# Sheet.net
KiCad netlist of a schematic drawn in Altium Designer
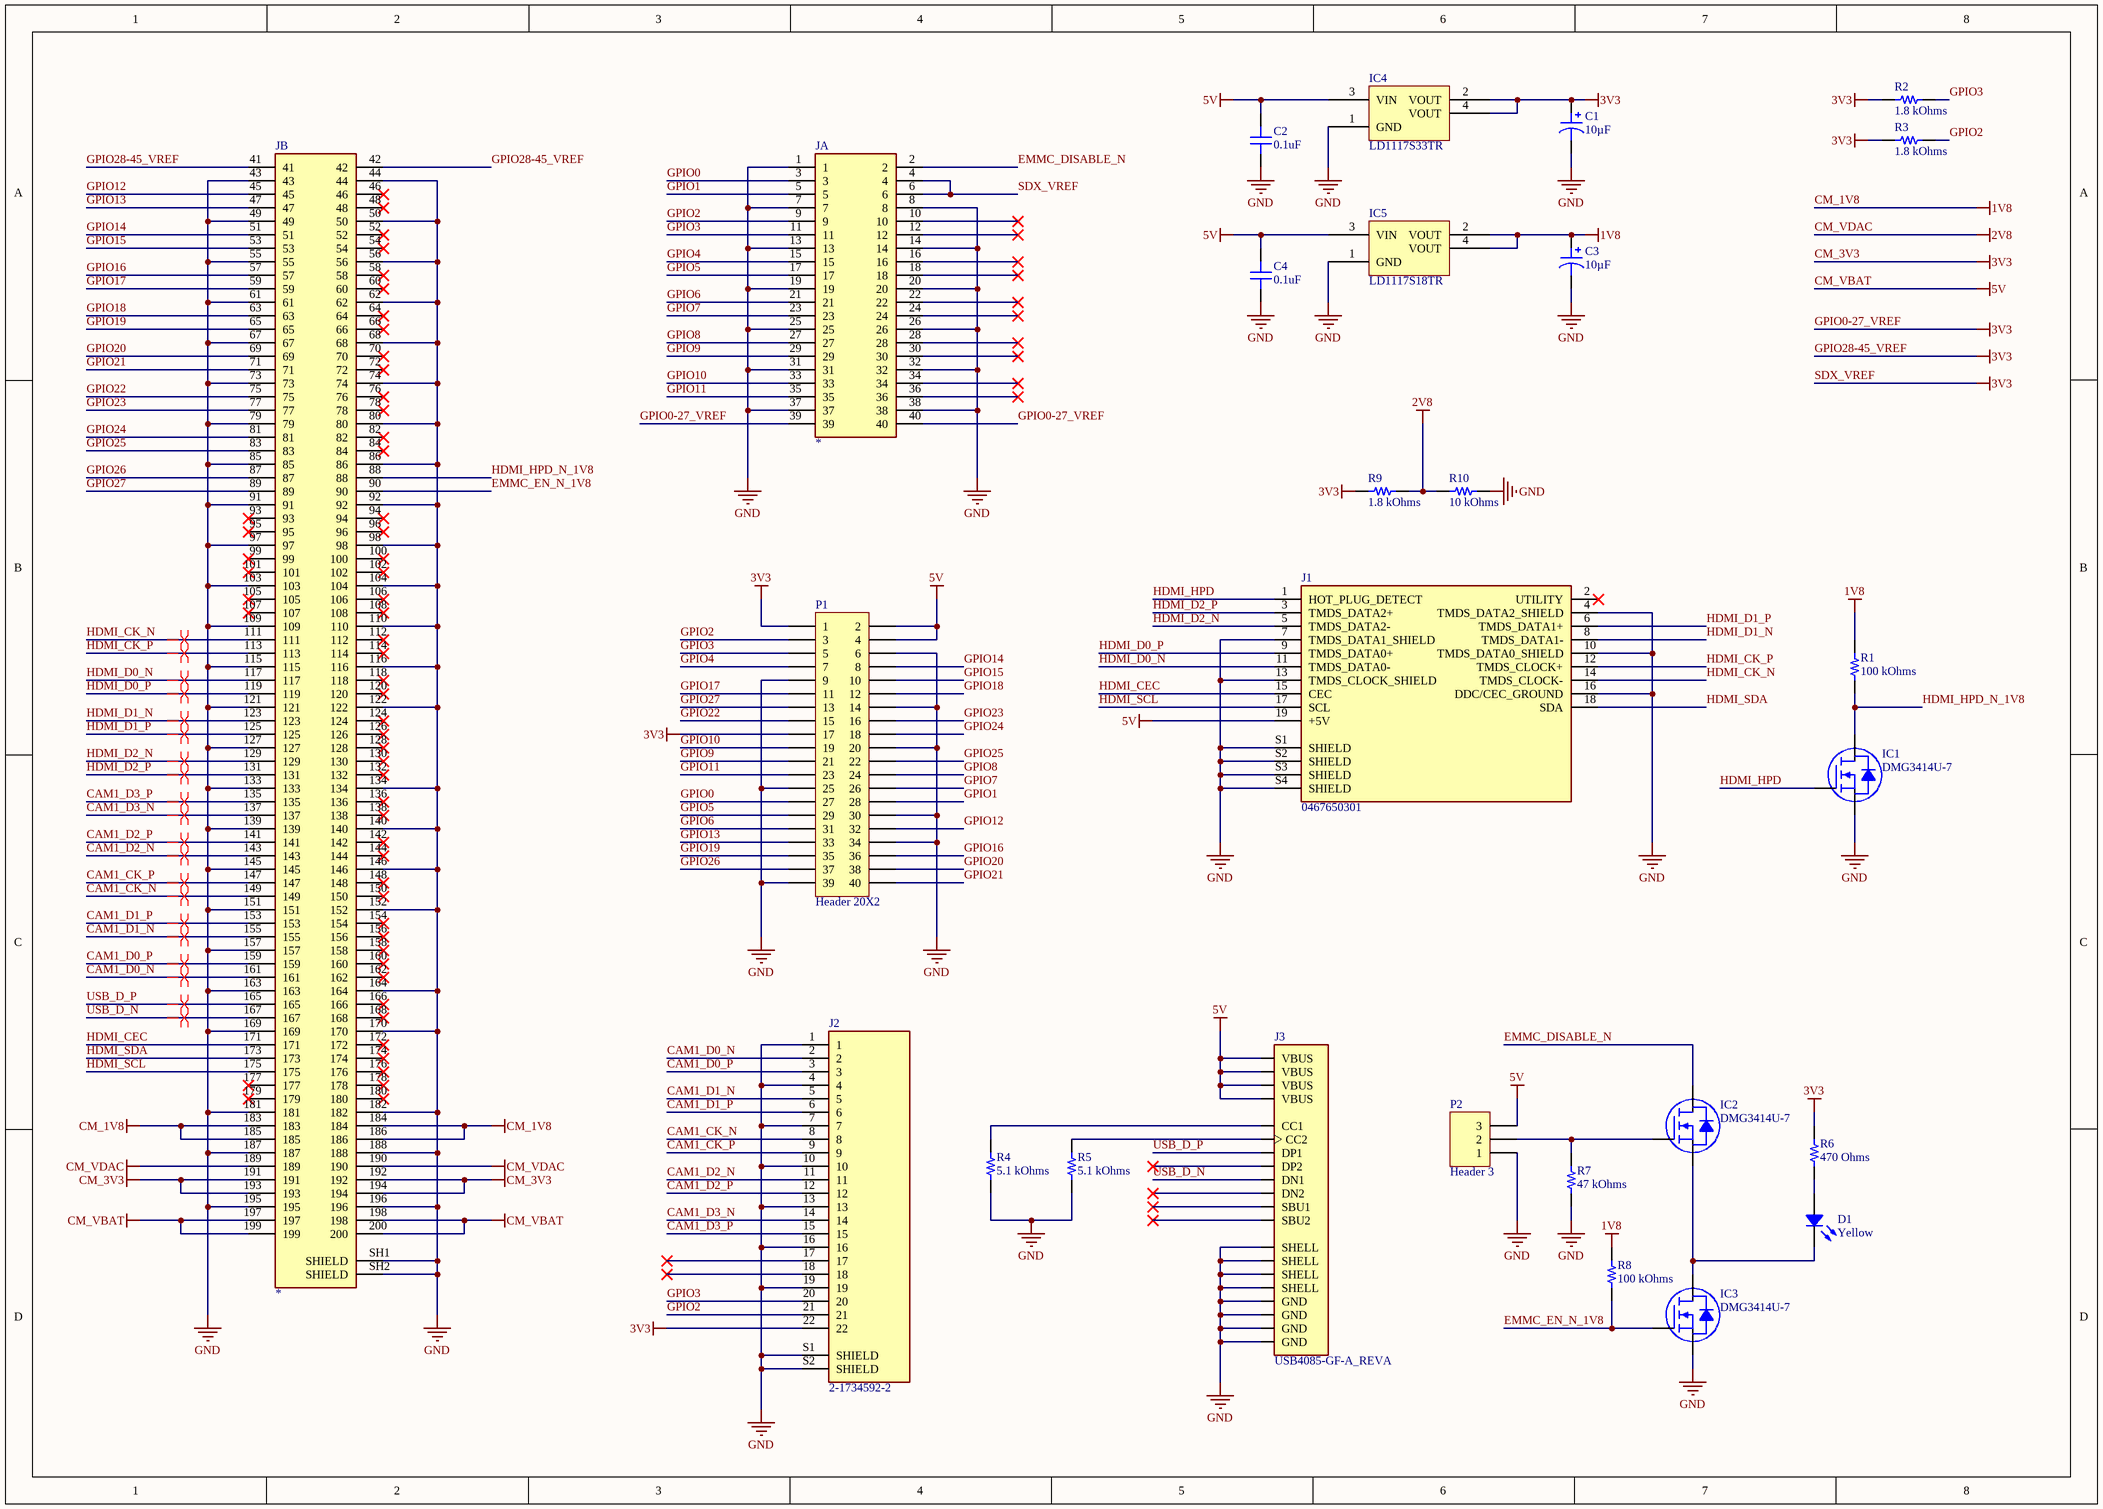
[diagram p0: Sheet.SchDoc]

(export (version "E")
  (design (tool "Eeschema 10.0.6"))
  (components
    (comp (ref "C1")
      (value "10µF")
      (footprint "CAP POL 1206_3216")
      (description "CAP TANT 4.7UF 10% 20V 1206")
      (fields (field (name "PART NUMBER") "TR3A475K020C1800") (field (name "MANUFACTURER") "Vishay Sprague"))
      (libsource (lib "Celestial Altium Library-altium_library") (part "Polarised Capacitor"))
    )
    (comp (ref "C2")
      (value "0.1uF")
      (footprint "CAP 0603_1608")
      (description "CAP CER 0.1uF 200V X7R 0603")
      (fields (field (name "PART NUMBER") "CC0603KRX7RABB102") (field (name "MANUFACTURER") "Yageo"))
      (libsource (lib "Celestial Altium Library-altium_library") (part "Capacitor"))
    )
    (comp (ref "C3")
      (value "10µF")
      (footprint "CAP POL 1206_3216")
      (description "CAP TANT 4.7UF 10% 20V 1206")
      (fields (field (name "PART NUMBER") "TR3A475K020C1800") (field (name "MANUFACTURER") "Vishay Sprague"))
      (libsource (lib "Celestial Altium Library-altium_library") (part "Polarised Capacitor"))
    )
    (comp (ref "C4")
      (value "0.1uF")
      (footprint "CAP 0603_1608")
      (description "CAP CER 0.1uF 200V X7R 0603")
      (fields (field (name "PART NUMBER") "CC0603KRX7RABB102") (field (name "MANUFACTURER") "Yageo"))
      (libsource (lib "Celestial Altium Library-altium_library") (part "Capacitor"))
    )
    (comp (ref "D1")
      (value "Yellow")
      (footprint "LED 0603_1608 YELLOW")
      (description "LED YELLOW DIFFUSED SMD")
      (fields (field (name "PART NUMBER") "FKY1111C-TR") (field (name "MANUFACTURER") "Stanley Electric Co"))
      (libsource (lib "Celestial Altium Library-altium_library") (part "LED"))
    )
    (comp (ref "IC1")
      (value "DMG3414U-7")
      (footprint "DIODES SOT-23-3")
      (description "MOSFET N-CH 20V 4.2A SOT23")
      (fields (field (name "MANUFACTURER") "Diodes Incorporated"))
      (libsource (lib "Celestial Altium Library-altium_library") (part "DIODES INC MOSFET N-CH SOT-23-3"))
    )
    (comp (ref "IC2")
      (value "DMG3414U-7")
      (footprint "DIODES SOT-23-3")
      (description "MOSFET N-CH 20V 4.2A SOT23")
      (fields (field (name "MANUFACTURER") "Diodes Incorporated"))
      (libsource (lib "Celestial Altium Library-altium_library") (part "DIODES INC MOSFET N-CH SOT-23-3"))
    )
    (comp (ref "IC3")
      (value "DMG3414U-7")
      (footprint "DIODES SOT-23-3")
      (description "MOSFET N-CH 20V 4.2A SOT23")
      (fields (field (name "MANUFACTURER") "Diodes Incorporated"))
      (libsource (lib "Celestial Altium Library-altium_library") (part "DIODES INC MOSFET N-CH SOT-23-3"))
    )
    (comp (ref "IC4")
      (value "LD1117S33TR")
      (footprint "ST SOT-223")
      (description "IC REG LINEAR 3.3V 800MA SOT223")
      (fields (field (name "MANUFACTURER") "STMicroelectronics"))
      (libsource (lib "Celestial Altium Library-altium_library") (part "ST LD1117"))
    )
    (comp (ref "IC5")
      (value "LD1117S18TR")
      (footprint "ST SOT-223")
      (description "IC REG LINEAR 1.8V 800MA SOT223")
      (fields (field (name "MANUFACTURER") "STMicroelectronics"))
      (libsource (lib "Celestial Altium Library-altium_library") (part "ST LD1117"))
    )
    (comp (ref "J")
      (value "1473149-4")
      (footprint "TE_1473149-4")
      (description "200 Position Dual Row 0.60mm Surface Mount Right Angle DIMM Memory Socket")
      (fields (field (name "MF") "TE Connectivity") (field (name "COMMENT_1") "*"))
      (libsource (lib "1473149-4") (part "1473149-4"))
    )
    (comp (ref "J1")
      (value "0467650301")
      (footprint "MOLEX_0467650301")
      (description "HDMI - Micro Receptacle Connector 19 Position Surface Mount, Right Angle")
      (fields (field (name "MF") "Molex"))
      (libsource (lib "0467650301") (part "0467650301"))
    )
    (comp (ref "J2")
      (value "2-1734592-2")
      (footprint "TE_2-1734592-2")
      (description "22 Position FPC Connector Contacts, Bottom 0.020 _0.50mm_ Surface Mount, Right Angle")
      (fields (field (name "MF") "TE Connectivity"))
      (libsource (lib "2-1734592-2") (part "2-1734592-2"))
    )
    (comp (ref "J3")
      (value "USB4085-GF-A_REVA")
      (footprint "GCT_USB4085-GF-A_REVA")
      (description "USB-C (USB TYPE-C) USB 2.0 Receptacle Connector 24 (16+8 Dummy) Position Through Hole, Right Angle")
      (fields (field (name "MF") "Global Connector Technology") (field (name "MP") "USB4085-GF-A"))
      (libsource (lib "USB4085-GF-A_REVA") (part "USB4085-GF-A_REVA"))
    )
    (comp (ref "P1")
      (value "Header 20X2")
      (footprint "HDR2X20")
      (description "Header, 20-Pin, Dual row")
      (fields (field (name "PUBLISHER") "Altium Limited"))
      (libsource (lib "Miscellaneous Connectors") (part "Header 20X2"))
    )
    (comp (ref "P2")
      (value "Header 3")
      (footprint "HDR1X3")
      (description "Header, 3-Pin")
      (fields (field (name "PUBLISHER") "Altium Limited"))
      (libsource (lib "Miscellaneous Connectors") (part "Header 3"))
    )
    (comp (ref "R1")
      (value "100 kOhms")
      (footprint "RES 0603_1608")
      (description "RES 100K OHM 0.1% 1/16W 0603")
      (fields
        (field (name "PART NUMBER") "RNCS0603BKE100K")
        (field (name "MANUFACTURER") "Stackpole Electronics Inc")
      )
      (libsource (lib "Celestial Altium Library-altium_library") (part "Resistor"))
    )
    (comp (ref "R2")
      (value "1.8 kOhms")
      (footprint "RES 0603_1608")
      (description "RES 1.8K OHM 5% 1/10W 0603")
      (fields
        (field (name "PART NUMBER") "RMCF0603JT1K80")
        (field (name "MANUFACTURER") "Stackpole Electronics Inc")
      )
      (libsource (lib "Celestial Altium Library-altium_library") (part "Resistor"))
    )
    (comp (ref "R3")
      (value "1.8 kOhms")
      (footprint "RES 0603_1608")
      (description "RES 1.8K OHM 5% 1/10W 0603")
      (fields
        (field (name "PART NUMBER") "RMCF0603JT1K80")
        (field (name "MANUFACTURER") "Stackpole Electronics Inc")
      )
      (libsource (lib "Celestial Altium Library-altium_library") (part "Resistor"))
    )
    (comp (ref "R4")
      (value "5.1 kOhms")
      (footprint "RES 0603_1608")
      (description "RES 5.1K OHM 5% 1/10W 0603")
      (fields
        (field (name "PART NUMBER") "RMCF0603JG5K10")
        (field (name "MANUFACTURER") "Stackpole Electronics Inc")
      )
      (libsource (lib "Celestial Altium Library-altium_library") (part "Resistor"))
    )
    (comp (ref "R5")
      (value "5.1 kOhms")
      (footprint "RES 0603_1608")
      (description "RES 5.1K OHM 5% 1/10W 0603")
      (fields
        (field (name "PART NUMBER") "RMCF0603JG5K10")
        (field (name "MANUFACTURER") "Stackpole Electronics Inc")
      )
      (libsource (lib "Celestial Altium Library-altium_library") (part "Resistor"))
    )
    (comp (ref "R6")
      (value "470 Ohms")
      (footprint "RES 0603_1608")
      (description "RES 470 OHM 1% 1/10W 0603")
      (fields
        (field (name "PART NUMBER") "RMCF0603FT470R")
        (field (name "MANUFACTURER") "Stackpole Electronics Inc")
      )
      (libsource (lib "Celestial Altium Library-altium_library") (part "Resistor"))
    )
    (comp (ref "R7")
      (value "47 kOhms")
      (footprint "RES 0603_1608")
      (description "RES SMD 47K OHM 0.1% 1/16W 0603")
      (fields
        (field (name "PART NUMBER") "CPF0603B47KE")
        (field (name "MANUFACTURER") "TE Connectivity Passive Product")
      )
      (libsource (lib "Celestial Altium Library-altium_library") (part "Resistor"))
    )
    (comp (ref "R8")
      (value "100 kOhms")
      (footprint "RES 0603_1608")
      (description "RES 100K OHM 0.1% 1/16W 0603")
      (fields
        (field (name "PART NUMBER") "RNCS0603BKE100K")
        (field (name "MANUFACTURER") "Stackpole Electronics Inc")
      )
      (libsource (lib "Celestial Altium Library-altium_library") (part "Resistor"))
    )
    (comp (ref "R9")
      (value "1.8 kOhms")
      (footprint "RES 0603_1608")
      (description "RES 1.8K OHM 5% 1/10W 0603")
      (fields
        (field (name "PART NUMBER") "RMCF0603JT1K80")
        (field (name "MANUFACTURER") "Stackpole Electronics Inc")
      )
      (libsource (lib "Celestial Altium Library-altium_library") (part "Resistor"))
    )
    (comp (ref "R10")
      (value "10 kOhms")
      (footprint "RES 0603_1608")
      (description "RES 10K OHM 0.1% 1/16W 0603")
      (fields
        (field (name "PART NUMBER") "RNCS0603BKE10K0")
        (field (name "MANUFACTURER") "Stackpole Electronics Inc")
      )
      (libsource (lib "Celestial Altium Library-altium_library") (part "Resistor"))
    )
  )
  (nets
    (net (code "1") (name "/CAM1_CK_N") (class "Default")
      (node (ref "J") (pin "149") (pinfunction "149_149") (pintype "passive"))
      (node (ref "J2") (pin "8") (pinfunction "8_8") (pintype "passive"))
    )
    (net (code "2") (name "/CAM1_CK_P") (class "Default")
      (node (ref "J") (pin "147") (pinfunction "147_147") (pintype "passive"))
      (node (ref "J2") (pin "9") (pinfunction "9_9") (pintype "passive"))
    )
    (net (code "3") (name "/CAM1_D0_N") (class "Default")
      (node (ref "J") (pin "161") (pinfunction "161_161") (pintype "passive"))
      (node (ref "J2") (pin "2") (pinfunction "2_2") (pintype "passive"))
    )
    (net (code "4") (name "/CAM1_D0_P") (class "Default")
      (node (ref "J") (pin "159") (pinfunction "159_159") (pintype "passive"))
      (node (ref "J2") (pin "3") (pinfunction "3_3") (pintype "passive"))
    )
    (net (code "5") (name "/CAM1_D1_N") (class "Default")
      (node (ref "J") (pin "155") (pinfunction "155_155") (pintype "passive"))
      (node (ref "J2") (pin "5") (pinfunction "5_5") (pintype "passive"))
    )
    (net (code "6") (name "/CAM1_D1_P") (class "Default")
      (node (ref "J") (pin "153") (pinfunction "153_153") (pintype "passive"))
      (node (ref "J2") (pin "6") (pinfunction "6_6") (pintype "passive"))
    )
    (net (code "7") (name "/CAM1_D2_N") (class "Default")
      (node (ref "J") (pin "143") (pinfunction "143_143") (pintype "passive"))
      (node (ref "J2") (pin "11") (pinfunction "11_11") (pintype "passive"))
    )
    (net (code "8") (name "/CAM1_D2_P") (class "Default")
      (node (ref "J") (pin "141") (pinfunction "141_141") (pintype "passive"))
      (node (ref "J2") (pin "12") (pinfunction "12_12") (pintype "passive"))
    )
    (net (code "9") (name "/CAM1_D3_N") (class "Default")
      (node (ref "J") (pin "137") (pinfunction "137_137") (pintype "passive"))
      (node (ref "J2") (pin "14") (pinfunction "14_14") (pintype "passive"))
    )
    (net (code "10") (name "/CAM1_D3_P") (class "Default")
      (node (ref "J") (pin "135") (pinfunction "135_135") (pintype "passive"))
      (node (ref "J2") (pin "15") (pinfunction "15_15") (pintype "passive"))
    )
    (net (code "11") (name "/EMMC_DISABLE_N") (class "Default")
      (node (ref "IC2") (pin "3") (pinfunction "D_3") (pintype "passive"))
      (node (ref "J") (pin "2") (pinfunction "2_2") (pintype "passive"))
    )
    (net (code "12") (name "/EMMC_EN_N_1V8") (class "Default")
      (node (ref "IC3") (pin "1") (pinfunction "G_1") (pintype "passive"))
      (node (ref "J") (pin "90") (pinfunction "90_90") (pintype "passive"))
      (node (ref "R8") (pin "1") (pinfunction "1_1") (pintype "passive"))
    )
    (net (code "13") (name "/GPIO0") (class "Default")
      (node (ref "J") (pin "3") (pinfunction "3_3") (pintype "passive"))
      (node (ref "P1") (pin "27") (pinfunction "27_27") (pintype "passive"))
    )
    (net (code "14") (name "/GPIO1") (class "Default")
      (node (ref "J") (pin "5") (pinfunction "5_5") (pintype "passive"))
      (node (ref "P1") (pin "28") (pinfunction "28_28") (pintype "passive"))
    )
    (net (code "15") (name "/GPIO2") (class "Default")
      (node (ref "J") (pin "9") (pinfunction "9_9") (pintype "passive"))
      (node (ref "J2") (pin "21") (pinfunction "21_21") (pintype "passive"))
      (node (ref "P1") (pin "3") (pinfunction "3_3") (pintype "passive"))
      (node (ref "R3") (pin "2") (pinfunction "2_2") (pintype "passive"))
    )
    (net (code "16") (name "/GPIO3") (class "Default")
      (node (ref "J") (pin "11") (pinfunction "11_11") (pintype "passive"))
      (node (ref "J2") (pin "20") (pinfunction "20_20") (pintype "passive"))
      (node (ref "P1") (pin "5") (pinfunction "5_5") (pintype "passive"))
      (node (ref "R2") (pin "2") (pinfunction "2_2") (pintype "passive"))
    )
    (net (code "17") (name "/GPIO4") (class "Default")
      (node (ref "J") (pin "15") (pinfunction "15_15") (pintype "passive"))
      (node (ref "P1") (pin "7") (pinfunction "7_7") (pintype "passive"))
    )
    (net (code "18") (name "/GPIO5") (class "Default")
      (node (ref "J") (pin "17") (pinfunction "17_17") (pintype "passive"))
      (node (ref "P1") (pin "29") (pinfunction "29_29") (pintype "passive"))
    )
    (net (code "19") (name "/GPIO6") (class "Default")
      (node (ref "J") (pin "21") (pinfunction "21_21") (pintype "passive"))
      (node (ref "P1") (pin "31") (pinfunction "31_31") (pintype "passive"))
    )
    (net (code "20") (name "/GPIO7") (class "Default")
      (node (ref "J") (pin "23") (pinfunction "23_23") (pintype "passive"))
      (node (ref "P1") (pin "26") (pinfunction "26_26") (pintype "passive"))
    )
    (net (code "21") (name "/GPIO8") (class "Default")
      (node (ref "J") (pin "27") (pinfunction "27_27") (pintype "passive"))
      (node (ref "P1") (pin "24") (pinfunction "24_24") (pintype "passive"))
    )
    (net (code "22") (name "/GPIO9") (class "Default")
      (node (ref "J") (pin "29") (pinfunction "29_29") (pintype "passive"))
      (node (ref "P1") (pin "21") (pinfunction "21_21") (pintype "passive"))
    )
    (net (code "23") (name "/GPIO10") (class "Default")
      (node (ref "J") (pin "33") (pinfunction "33_33") (pintype "passive"))
      (node (ref "P1") (pin "19") (pinfunction "19_19") (pintype "passive"))
    )
    (net (code "24") (name "/GPIO11") (class "Default")
      (node (ref "J") (pin "35") (pinfunction "35_35") (pintype "passive"))
      (node (ref "P1") (pin "23") (pinfunction "23_23") (pintype "passive"))
    )
    (net (code "25") (name "/GPIO12") (class "Default")
      (node (ref "J") (pin "45") (pinfunction "45_45") (pintype "passive"))
      (node (ref "P1") (pin "32") (pinfunction "32_32") (pintype "passive"))
    )
    (net (code "26") (name "/GPIO13") (class "Default")
      (node (ref "J") (pin "47") (pinfunction "47_47") (pintype "passive"))
      (node (ref "P1") (pin "33") (pinfunction "33_33") (pintype "passive"))
    )
    (net (code "27") (name "/GPIO14") (class "Default")
      (node (ref "J") (pin "51") (pinfunction "51_51") (pintype "passive"))
      (node (ref "P1") (pin "8") (pinfunction "8_8") (pintype "passive"))
    )
    (net (code "28") (name "/GPIO15") (class "Default")
      (node (ref "J") (pin "53") (pinfunction "53_53") (pintype "passive"))
      (node (ref "P1") (pin "10") (pinfunction "10_10") (pintype "passive"))
    )
    (net (code "29") (name "/GPIO16") (class "Default")
      (node (ref "J") (pin "57") (pinfunction "57_57") (pintype "passive"))
      (node (ref "P1") (pin "36") (pinfunction "36_36") (pintype "passive"))
    )
    (net (code "30") (name "/GPIO17") (class "Default")
      (node (ref "J") (pin "59") (pinfunction "59_59") (pintype "passive"))
      (node (ref "P1") (pin "11") (pinfunction "11_11") (pintype "passive"))
    )
    (net (code "31") (name "/GPIO18") (class "Default")
      (node (ref "J") (pin "63") (pinfunction "63_63") (pintype "passive"))
      (node (ref "P1") (pin "12") (pinfunction "12_12") (pintype "passive"))
    )
    (net (code "32") (name "/GPIO19") (class "Default")
      (node (ref "J") (pin "65") (pinfunction "65_65") (pintype "passive"))
      (node (ref "P1") (pin "35") (pinfunction "35_35") (pintype "passive"))
    )
    (net (code "33") (name "/GPIO20") (class "Default")
      (node (ref "J") (pin "69") (pinfunction "69_69") (pintype "passive"))
      (node (ref "P1") (pin "38") (pinfunction "38_38") (pintype "passive"))
    )
    (net (code "34") (name "/GPIO21") (class "Default")
      (node (ref "J") (pin "71") (pinfunction "71_71") (pintype "passive"))
      (node (ref "P1") (pin "40") (pinfunction "40_40") (pintype "passive"))
    )
    (net (code "35") (name "/GPIO22") (class "Default")
      (node (ref "J") (pin "75") (pinfunction "75_75") (pintype "passive"))
      (node (ref "P1") (pin "15") (pinfunction "15_15") (pintype "passive"))
    )
    (net (code "36") (name "/GPIO23") (class "Default")
      (node (ref "J") (pin "77") (pinfunction "77_77") (pintype "passive"))
      (node (ref "P1") (pin "16") (pinfunction "16_16") (pintype "passive"))
    )
    (net (code "37") (name "/GPIO24") (class "Default")
      (node (ref "J") (pin "81") (pinfunction "81_81") (pintype "passive"))
      (node (ref "P1") (pin "18") (pinfunction "18_18") (pintype "passive"))
    )
    (net (code "38") (name "/GPIO25") (class "Default")
      (node (ref "J") (pin "83") (pinfunction "83_83") (pintype "passive"))
      (node (ref "P1") (pin "22") (pinfunction "22_22") (pintype "passive"))
    )
    (net (code "39") (name "/GPIO26") (class "Default")
      (node (ref "J") (pin "87") (pinfunction "87_87") (pintype "passive"))
      (node (ref "P1") (pin "37") (pinfunction "37_37") (pintype "passive"))
    )
    (net (code "40") (name "/GPIO27") (class "Default")
      (node (ref "J") (pin "89") (pinfunction "89_89") (pintype "passive"))
      (node (ref "P1") (pin "13") (pinfunction "13_13") (pintype "passive"))
    )
    (net (code "41") (name "/HDMI_CEC") (class "Default")
      (node (ref "J") (pin "171") (pinfunction "171_171") (pintype "passive"))
      (node (ref "J1") (pin "15") (pinfunction "CEC_15") (pintype "passive"))
    )
    (net (code "42") (name "/HDMI_CK_N") (class "Default")
      (node (ref "J") (pin "111") (pinfunction "111_111") (pintype "passive"))
      (node (ref "J1") (pin "14") (pinfunction "TMDS_CLOCK-_14") (pintype "passive"))
    )
    (net (code "43") (name "/HDMI_CK_P") (class "Default")
      (node (ref "J") (pin "113") (pinfunction "113_113") (pintype "passive"))
      (node (ref "J1") (pin "12") (pinfunction "TMDS_CLOCK+_12") (pintype "passive"))
    )
    (net (code "44") (name "/HDMI_D0_N") (class "Default")
      (node (ref "J") (pin "117") (pinfunction "117_117") (pintype "passive"))
      (node (ref "J1") (pin "11") (pinfunction "TMDS_DATA0-_11") (pintype "passive"))
    )
    (net (code "45") (name "/HDMI_D0_P") (class "Default")
      (node (ref "J") (pin "119") (pinfunction "119_119") (pintype "passive"))
      (node (ref "J1") (pin "9") (pinfunction "TMDS_DATA0+_9") (pintype "passive"))
    )
    (net (code "46") (name "/HDMI_D1_N") (class "Default")
      (node (ref "J") (pin "123") (pinfunction "123_123") (pintype "passive"))
      (node (ref "J1") (pin "8") (pinfunction "TMDS_DATA1-_8") (pintype "passive"))
    )
    (net (code "47") (name "/HDMI_D1_P") (class "Default")
      (node (ref "J") (pin "125") (pinfunction "125_125") (pintype "passive"))
      (node (ref "J1") (pin "6") (pinfunction "TMDS_DATA1+_6") (pintype "passive"))
    )
    (net (code "48") (name "/HDMI_D2_N") (class "Default")
      (node (ref "J") (pin "129") (pinfunction "129_129") (pintype "passive"))
      (node (ref "J1") (pin "5") (pinfunction "TMDS_DATA2-_5") (pintype "passive"))
    )
    (net (code "49") (name "/HDMI_D2_P") (class "Default")
      (node (ref "J") (pin "131") (pinfunction "131_131") (pintype "passive"))
      (node (ref "J1") (pin "3") (pinfunction "TMDS_DATA2+_3") (pintype "passive"))
    )
    (net (code "50") (name "/HDMI_HPD") (class "Default")
      (node (ref "IC1") (pin "1") (pinfunction "G_1") (pintype "passive"))
      (node (ref "J1") (pin "1") (pinfunction "HOT_PLUG_DETECT_1") (pintype "passive"))
    )
    (net (code "51") (name "/HDMI_HPD_N_1V8") (class "Default")
      (node (ref "IC1") (pin "3") (pinfunction "D_3") (pintype "passive"))
      (node (ref "J") (pin "88") (pinfunction "88_88") (pintype "passive"))
      (node (ref "R1") (pin "1") (pinfunction "1_1") (pintype "passive"))
    )
    (net (code "52") (name "/HDMI_SCL") (class "Default")
      (node (ref "J") (pin "175") (pinfunction "175_175") (pintype "passive"))
      (node (ref "J1") (pin "17") (pinfunction "SCL_17") (pintype "passive"))
    )
    (net (code "53") (name "/HDMI_SDA") (class "Default")
      (node (ref "J") (pin "173") (pinfunction "173_173") (pintype "passive"))
      (node (ref "J1") (pin "18") (pinfunction "SDA_18") (pintype "passive"))
    )
    (net (code "54") (name "/USB_D_N") (class "Default")
      (node (ref "J") (pin "167") (pinfunction "167_167") (pintype "passive"))
      (node (ref "J3") (pin "A7") (pinfunction "DN1_A7") (pintype "bidirectional"))
    )
    (net (code "55") (name "/USB_D_P") (class "Default")
      (node (ref "J") (pin "165") (pinfunction "165_165") (pintype "passive"))
      (node (ref "J3") (pin "A6") (pinfunction "DP1_A6") (pintype "bidirectional"))
    )
    (net (code "56") (name "1V8") (class "Default")
      (node (ref "C3") (pin "1") (pinfunction "1_1") (pintype "passive"))
      (node (ref "IC5") (pin "2") (pinfunction "VOUT_2") (pintype "passive"))
      (node (ref "IC5") (pin "4") (pinfunction "VOUT_4") (pintype "passive"))
      (node (ref "J") (pin "183") (pinfunction "183_183") (pintype "passive"))
      (node (ref "J") (pin "184") (pinfunction "184_184") (pintype "passive"))
      (node (ref "J") (pin "185") (pinfunction "185_185") (pintype "passive"))
      (node (ref "J") (pin "186") (pinfunction "186_186") (pintype "passive"))
      (node (ref "R1") (pin "2") (pinfunction "2_2") (pintype "passive"))
      (node (ref "R8") (pin "2") (pinfunction "2_2") (pintype "passive"))
    )
    (net (code "57") (name "2V8") (class "Default")
      (node (ref "J") (pin "189") (pinfunction "189_189") (pintype "passive"))
      (node (ref "J") (pin "190") (pinfunction "190_190") (pintype "passive"))
      (node (ref "R10") (pin "2") (pinfunction "2_2") (pintype "passive"))
      (node (ref "R9") (pin "1") (pinfunction "1_1") (pintype "passive"))
    )
    (net (code "58") (name "3V3") (class "Default")
      (node (ref "C1") (pin "1") (pinfunction "1_1") (pintype "passive"))
      (node (ref "IC4") (pin "2") (pinfunction "VOUT_2") (pintype "passive"))
      (node (ref "IC4") (pin "4") (pinfunction "VOUT_4") (pintype "passive"))
      (node (ref "J") (pin "191") (pinfunction "191_191") (pintype "passive"))
      (node (ref "J") (pin "192") (pinfunction "192_192") (pintype "passive"))
      (node (ref "J") (pin "193") (pinfunction "193_193") (pintype "passive"))
      (node (ref "J") (pin "194") (pinfunction "194_194") (pintype "passive"))
      (node (ref "J") (pin "39") (pinfunction "39_39") (pintype "passive"))
      (node (ref "J") (pin "4") (pinfunction "4_4") (pintype "passive"))
      (node (ref "J") (pin "40") (pinfunction "40_40") (pintype "passive"))
      (node (ref "J") (pin "41") (pinfunction "41_41") (pintype "passive"))
      (node (ref "J") (pin "42") (pinfunction "42_42") (pintype "passive"))
      (node (ref "J") (pin "6") (pinfunction "6_6") (pintype "passive"))
      (node (ref "J2") (pin "22") (pinfunction "22_22") (pintype "passive"))
      (node (ref "P1") (pin "1") (pinfunction "1_1") (pintype "passive"))
      (node (ref "P1") (pin "17") (pinfunction "17_17") (pintype "passive"))
      (node (ref "R2") (pin "1") (pinfunction "1_1") (pintype "passive"))
      (node (ref "R3") (pin "1") (pinfunction "1_1") (pintype "passive"))
      (node (ref "R6") (pin "2") (pinfunction "2_2") (pintype "passive"))
      (node (ref "R9") (pin "2") (pinfunction "2_2") (pintype "passive"))
    )
    (net (code "59") (name "5V") (class "Default")
      (node (ref "C2") (pin "2") (pinfunction "2_2") (pintype "passive"))
      (node (ref "C4") (pin "2") (pinfunction "2_2") (pintype "passive"))
      (node (ref "IC4") (pin "3") (pinfunction "VIN_3") (pintype "passive"))
      (node (ref "IC5") (pin "3") (pinfunction "VIN_3") (pintype "passive"))
      (node (ref "J") (pin "197") (pinfunction "197_197") (pintype "passive"))
      (node (ref "J") (pin "198") (pinfunction "198_198") (pintype "passive"))
      (node (ref "J") (pin "199") (pinfunction "199_199") (pintype "passive"))
      (node (ref "J") (pin "200") (pinfunction "200_200") (pintype "passive"))
      (node (ref "J1") (pin "19") (pinfunction "+5V_19") (pintype "passive"))
      (node (ref "J3") (pin "A4") (pinfunction "VBUS_A4") (pintype "power_in"))
      (node (ref "J3") (pin "A9") (pinfunction "VBUS_A9") (pintype "power_in"))
      (node (ref "J3") (pin "B4") (pinfunction "VBUS_B4") (pintype "power_in"))
      (node (ref "J3") (pin "B9") (pinfunction "VBUS_B9") (pintype "power_in"))
      (node (ref "P1") (pin "2") (pinfunction "2_2") (pintype "passive"))
      (node (ref "P1") (pin "4") (pinfunction "4_4") (pintype "passive"))
      (node (ref "P2") (pin "3") (pinfunction "3_3") (pintype "passive"))
    )
    (net (code "60") (name "GND") (class "Default")
      (node (ref "C1") (pin "2") (pinfunction "2_2") (pintype "passive"))
      (node (ref "C2") (pin "1") (pinfunction "1_1") (pintype "passive"))
      (node (ref "C3") (pin "2") (pinfunction "2_2") (pintype "passive"))
      (node (ref "C4") (pin "1") (pinfunction "1_1") (pintype "passive"))
      (node (ref "IC1") (pin "2") (pinfunction "S_2") (pintype "passive"))
      (node (ref "IC3") (pin "2") (pinfunction "S_2") (pintype "passive"))
      (node (ref "IC4") (pin "1") (pinfunction "GND_1") (pintype "passive"))
      (node (ref "IC5") (pin "1") (pinfunction "GND_1") (pintype "passive"))
      (node (ref "J") (pin "1") (pinfunction "1_1") (pintype "passive"))
      (node (ref "J") (pin "103") (pinfunction "103_103") (pintype "passive"))
      (node (ref "J") (pin "104") (pinfunction "104_104") (pintype "passive"))
      (node (ref "J") (pin "109") (pinfunction "109_109") (pintype "passive"))
      (node (ref "J") (pin "110") (pinfunction "110_110") (pintype "passive"))
      (node (ref "J") (pin "115") (pinfunction "115_115") (pintype "passive"))
      (node (ref "J") (pin "116") (pinfunction "116_116") (pintype "passive"))
      (node (ref "J") (pin "121") (pinfunction "121_121") (pintype "passive"))
      (node (ref "J") (pin "122") (pinfunction "122_122") (pintype "passive"))
      (node (ref "J") (pin "127") (pinfunction "127_127") (pintype "passive"))
      (node (ref "J") (pin "13") (pinfunction "13_13") (pintype "passive"))
      (node (ref "J") (pin "133") (pinfunction "133_133") (pintype "passive"))
      (node (ref "J") (pin "134") (pinfunction "134_134") (pintype "passive"))
      (node (ref "J") (pin "139") (pinfunction "139_139") (pintype "passive"))
      (node (ref "J") (pin "14") (pinfunction "14_14") (pintype "passive"))
      (node (ref "J") (pin "140") (pinfunction "140_140") (pintype "passive"))
      (node (ref "J") (pin "145") (pinfunction "145_145") (pintype "passive"))
      (node (ref "J") (pin "146") (pinfunction "146_146") (pintype "passive"))
      (node (ref "J") (pin "151") (pinfunction "151_151") (pintype "passive"))
      (node (ref "J") (pin "152") (pinfunction "152_152") (pintype "passive"))
      (node (ref "J") (pin "157") (pinfunction "157_157") (pintype "passive"))
      (node (ref "J") (pin "163") (pinfunction "163_163") (pintype "passive"))
      (node (ref "J") (pin "164") (pinfunction "164_164") (pintype "passive"))
      (node (ref "J") (pin "169") (pinfunction "169_169") (pintype "passive"))
      (node (ref "J") (pin "170") (pinfunction "170_170") (pintype "passive"))
      (node (ref "J") (pin "181") (pinfunction "181_181") (pintype "passive"))
      (node (ref "J") (pin "182") (pinfunction "182_182") (pintype "passive"))
      (node (ref "J") (pin "187") (pinfunction "187_187") (pintype "passive"))
      (node (ref "J") (pin "188") (pinfunction "188_188") (pintype "passive"))
      (node (ref "J") (pin "19") (pinfunction "19_19") (pintype "passive"))
      (node (ref "J") (pin "195") (pinfunction "195_195") (pintype "passive"))
      (node (ref "J") (pin "196") (pinfunction "196_196") (pintype "passive"))
      (node (ref "J") (pin "20") (pinfunction "20_20") (pintype "passive"))
      (node (ref "J") (pin "25") (pinfunction "25_25") (pintype "passive"))
      (node (ref "J") (pin "26") (pinfunction "26_26") (pintype "passive"))
      (node (ref "J") (pin "31") (pinfunction "31_31") (pintype "passive"))
      (node (ref "J") (pin "32") (pinfunction "32_32") (pintype "passive"))
      (node (ref "J") (pin "37") (pinfunction "37_37") (pintype "passive"))
      (node (ref "J") (pin "38") (pinfunction "38_38") (pintype "passive"))
      (node (ref "J") (pin "43") (pinfunction "43_43") (pintype "passive"))
      (node (ref "J") (pin "44") (pinfunction "44_44") (pintype "passive"))
      (node (ref "J") (pin "49") (pinfunction "49_49") (pintype "passive"))
      (node (ref "J") (pin "50") (pinfunction "50_50") (pintype "passive"))
      (node (ref "J") (pin "55") (pinfunction "55_55") (pintype "passive"))
      (node (ref "J") (pin "56") (pinfunction "56_56") (pintype "passive"))
      (node (ref "J") (pin "61") (pinfunction "61_61") (pintype "passive"))
      (node (ref "J") (pin "62") (pinfunction "62_62") (pintype "passive"))
      (node (ref "J") (pin "67") (pinfunction "67_67") (pintype "passive"))
      (node (ref "J") (pin "68") (pinfunction "68_68") (pintype "passive"))
      (node (ref "J") (pin "7") (pinfunction "7_7") (pintype "passive"))
      (node (ref "J") (pin "73") (pinfunction "73_73") (pintype "passive"))
      (node (ref "J") (pin "74") (pinfunction "74_74") (pintype "passive"))
      (node (ref "J") (pin "79") (pinfunction "79_79") (pintype "passive"))
      (node (ref "J") (pin "8") (pinfunction "8_8") (pintype "passive"))
      (node (ref "J") (pin "80") (pinfunction "80_80") (pintype "passive"))
      (node (ref "J") (pin "85") (pinfunction "85_85") (pintype "passive"))
      (node (ref "J") (pin "86") (pinfunction "86_86") (pintype "passive"))
      (node (ref "J") (pin "91") (pinfunction "91_91") (pintype "passive"))
      (node (ref "J") (pin "92") (pinfunction "92_92") (pintype "passive"))
      (node (ref "J") (pin "97") (pinfunction "97_97") (pintype "passive"))
      (node (ref "J") (pin "98") (pinfunction "98_98") (pintype "passive"))
      (node (ref "J") (pin "SH1") (pinfunction "SHIELD_SH1") (pintype "passive"))
      (node (ref "J") (pin "SH2") (pinfunction "SHIELD_SH2") (pintype "passive"))
      (node (ref "J1") (pin "10") (pinfunction "TMDS_DATA0_SHIELD_10") (pintype "passive"))
      (node (ref "J1") (pin "13") (pinfunction "TMDS_CLOCK_SHIELD_13") (pintype "passive"))
      (node (ref "J1") (pin "16") (pinfunction "DDC/CEC_GROUND_16") (pintype "passive"))
      (node (ref "J1") (pin "4") (pinfunction "TMDS_DATA2_SHIELD_4") (pintype "passive"))
      (node (ref "J1") (pin "7") (pinfunction "TMDS_DATA1_SHIELD_7") (pintype "passive"))
      (node (ref "J1") (pin "S1") (pinfunction "SHIELD_S1") (pintype "passive"))
      (node (ref "J1") (pin "S2") (pinfunction "SHIELD_S2") (pintype "passive"))
      (node (ref "J1") (pin "S3") (pinfunction "SHIELD_S3") (pintype "passive"))
      (node (ref "J1") (pin "S4") (pinfunction "SHIELD_S4") (pintype "passive"))
      (node (ref "J2") (pin "1") (pinfunction "1_1") (pintype "passive"))
      (node (ref "J2") (pin "10") (pinfunction "10_10") (pintype "passive"))
      (node (ref "J2") (pin "13") (pinfunction "13_13") (pintype "passive"))
      (node (ref "J2") (pin "16") (pinfunction "16_16") (pintype "passive"))
      (node (ref "J2") (pin "19") (pinfunction "19_19") (pintype "passive"))
      (node (ref "J2") (pin "4") (pinfunction "4_4") (pintype "passive"))
      (node (ref "J2") (pin "7") (pinfunction "7_7") (pintype "passive"))
      (node (ref "J2") (pin "S1") (pinfunction "SHIELD_S1") (pintype "passive"))
      (node (ref "J2") (pin "S2") (pinfunction "SHIELD_S2") (pintype "passive"))
      (node (ref "J3") (pin "A1") (pinfunction "GND_A1") (pintype "passive"))
      (node (ref "J3") (pin "A12") (pinfunction "GND_A12") (pintype "passive"))
      (node (ref "J3") (pin "B1") (pinfunction "GND_B1") (pintype "passive"))
      (node (ref "J3") (pin "B12") (pinfunction "GND_B12") (pintype "passive"))
      (node (ref "J3") (pin "P1") (pinfunction "SHELL_P1") (pintype "passive"))
      (node (ref "J3") (pin "P2") (pinfunction "SHELL_P2") (pintype "passive"))
      (node (ref "J3") (pin "P3") (pinfunction "SHELL_P3") (pintype "passive"))
      (node (ref "J3") (pin "P4") (pinfunction "SHELL_P4") (pintype "passive"))
      (node (ref "P1") (pin "14") (pinfunction "14_14") (pintype "passive"))
      (node (ref "P1") (pin "20") (pinfunction "20_20") (pintype "passive"))
      (node (ref "P1") (pin "25") (pinfunction "25_25") (pintype "passive"))
      (node (ref "P1") (pin "30") (pinfunction "30_30") (pintype "passive"))
      (node (ref "P1") (pin "34") (pinfunction "34_34") (pintype "passive"))
      (node (ref "P1") (pin "39") (pinfunction "39_39") (pintype "passive"))
      (node (ref "P1") (pin "6") (pinfunction "6_6") (pintype "passive"))
      (node (ref "P1") (pin "9") (pinfunction "9_9") (pintype "passive"))
      (node (ref "P2") (pin "1") (pinfunction "1_1") (pintype "passive"))
      (node (ref "R10") (pin "1") (pinfunction "1_1") (pintype "passive"))
      (node (ref "R4") (pin "1") (pinfunction "1_1") (pintype "passive"))
      (node (ref "R5") (pin "1") (pinfunction "1_1") (pintype "passive"))
      (node (ref "R7") (pin "1") (pinfunction "1_1") (pintype "passive"))
    )
    (net (code "61") (name "Net-(D1-Pad1)") (class "Default")
      (node (ref "D1") (pin "1") (pinfunction "1_1") (pintype "passive"))
      (node (ref "R6") (pin "1") (pinfunction "1_1") (pintype "passive"))
    )
    (net (code "62") (name "Net-(IC2-G)") (class "Default")
      (node (ref "IC2") (pin "1") (pinfunction "G_1") (pintype "passive"))
      (node (ref "P2") (pin "2") (pinfunction "2_2") (pintype "passive"))
      (node (ref "R7") (pin "2") (pinfunction "2_2") (pintype "passive"))
    )
    (net (code "63") (name "Net-(IC2-S)") (class "Default")
      (node (ref "D1") (pin "2") (pinfunction "2_2") (pintype "passive"))
      (node (ref "IC2") (pin "2") (pinfunction "S_2") (pintype "passive"))
      (node (ref "IC3") (pin "3") (pinfunction "D_3") (pintype "passive"))
    )
    (net (code "64") (name "Net-(J3-CC1)") (class "Default")
      (node (ref "J3") (pin "A5") (pinfunction "CC1_A5") (pintype "bidirectional"))
      (node (ref "R4") (pin "2") (pinfunction "2_2") (pintype "passive"))
    )
    (net (code "65") (name "Net-(J3-CC2)") (class "Default")
      (node (ref "J3") (pin "B5") (pinfunction "CC2_B5") (pintype "bidirectional"))
      (node (ref "R5") (pin "2") (pinfunction "2_2") (pintype "passive"))
    )
    (net (code "66") (name "unconnected-(J-Pad10)") (class "Default")
      (node (ref "J") (pin "10") (pinfunction "10_10") (pintype "passive+no_connect"))
    )
    (net (code "67") (name "unconnected-(J-Pad12)") (class "Default")
      (node (ref "J") (pin "12") (pinfunction "12_12") (pintype "passive+no_connect"))
    )
    (net (code "68") (name "unconnected-(J-Pad16)") (class "Default")
      (node (ref "J") (pin "16") (pinfunction "16_16") (pintype "passive+no_connect"))
    )
    (net (code "69") (name "unconnected-(J-Pad18)") (class "Default")
      (node (ref "J") (pin "18") (pinfunction "18_18") (pintype "passive+no_connect"))
    )
    (net (code "70") (name "unconnected-(J-Pad22)") (class "Default")
      (node (ref "J") (pin "22") (pinfunction "22_22") (pintype "passive+no_connect"))
    )
    (net (code "71") (name "unconnected-(J-Pad24)") (class "Default")
      (node (ref "J") (pin "24") (pinfunction "24_24") (pintype "passive+no_connect"))
    )
    (net (code "72") (name "unconnected-(J-Pad28)") (class "Default")
      (node (ref "J") (pin "28") (pinfunction "28_28") (pintype "passive+no_connect"))
    )
    (net (code "73") (name "unconnected-(J-Pad30)") (class "Default")
      (node (ref "J") (pin "30") (pinfunction "30_30") (pintype "passive+no_connect"))
    )
    (net (code "74") (name "unconnected-(J-Pad34)") (class "Default")
      (node (ref "J") (pin "34") (pinfunction "34_34") (pintype "passive+no_connect"))
    )
    (net (code "75") (name "unconnected-(J-Pad36)") (class "Default")
      (node (ref "J") (pin "36") (pinfunction "36_36") (pintype "passive+no_connect"))
    )
    (net (code "76") (name "unconnected-(J-Pad46)") (class "Default")
      (node (ref "J") (pin "46") (pinfunction "46_46") (pintype "passive+no_connect"))
    )
    (net (code "77") (name "unconnected-(J-Pad48)") (class "Default")
      (node (ref "J") (pin "48") (pinfunction "48_48") (pintype "passive+no_connect"))
    )
    (net (code "78") (name "unconnected-(J-Pad52)") (class "Default")
      (node (ref "J") (pin "52") (pinfunction "52_52") (pintype "passive+no_connect"))
    )
    (net (code "79") (name "unconnected-(J-Pad54)") (class "Default")
      (node (ref "J") (pin "54") (pinfunction "54_54") (pintype "passive+no_connect"))
    )
    (net (code "80") (name "unconnected-(J-Pad58)") (class "Default")
      (node (ref "J") (pin "58") (pinfunction "58_58") (pintype "passive+no_connect"))
    )
    (net (code "81") (name "unconnected-(J-Pad60)") (class "Default")
      (node (ref "J") (pin "60") (pinfunction "60_60") (pintype "passive+no_connect"))
    )
    (net (code "82") (name "unconnected-(J-Pad64)") (class "Default")
      (node (ref "J") (pin "64") (pinfunction "64_64") (pintype "passive+no_connect"))
    )
    (net (code "83") (name "unconnected-(J-Pad66)") (class "Default")
      (node (ref "J") (pin "66") (pinfunction "66_66") (pintype "passive+no_connect"))
    )
    (net (code "84") (name "unconnected-(J-Pad70)") (class "Default")
      (node (ref "J") (pin "70") (pinfunction "70_70") (pintype "passive+no_connect"))
    )
    (net (code "85") (name "unconnected-(J-Pad72)") (class "Default")
      (node (ref "J") (pin "72") (pinfunction "72_72") (pintype "passive+no_connect"))
    )
    (net (code "86") (name "unconnected-(J-Pad76)") (class "Default")
      (node (ref "J") (pin "76") (pinfunction "76_76") (pintype "passive+no_connect"))
    )
    (net (code "87") (name "unconnected-(J-Pad78)") (class "Default")
      (node (ref "J") (pin "78") (pinfunction "78_78") (pintype "passive+no_connect"))
    )
    (net (code "88") (name "unconnected-(J-Pad82)") (class "Default")
      (node (ref "J") (pin "82") (pinfunction "82_82") (pintype "passive+no_connect"))
    )
    (net (code "89") (name "unconnected-(J-Pad84)") (class "Default")
      (node (ref "J") (pin "84") (pinfunction "84_84") (pintype "passive+no_connect"))
    )
    (net (code "90") (name "unconnected-(J-Pad93)") (class "Default")
      (node (ref "J") (pin "93") (pinfunction "93_93") (pintype "passive+no_connect"))
    )
    (net (code "91") (name "unconnected-(J-Pad94)") (class "Default")
      (node (ref "J") (pin "94") (pinfunction "94_94") (pintype "passive+no_connect"))
    )
    (net (code "92") (name "unconnected-(J-Pad95)") (class "Default")
      (node (ref "J") (pin "95") (pinfunction "95_95") (pintype "passive+no_connect"))
    )
    (net (code "93") (name "unconnected-(J-Pad96)") (class "Default")
      (node (ref "J") (pin "96") (pinfunction "96_96") (pintype "passive+no_connect"))
    )
    (net (code "94") (name "unconnected-(J-Pad99)") (class "Default")
      (node (ref "J") (pin "99") (pinfunction "99_99") (pintype "passive+no_connect"))
    )
    (net (code "95") (name "unconnected-(J-Pad100)") (class "Default")
      (node (ref "J") (pin "100") (pinfunction "100_100") (pintype "passive+no_connect"))
    )
    (net (code "96") (name "unconnected-(J-Pad101)") (class "Default")
      (node (ref "J") (pin "101") (pinfunction "101_101") (pintype "passive+no_connect"))
    )
    (net (code "97") (name "unconnected-(J-Pad102)") (class "Default")
      (node (ref "J") (pin "102") (pinfunction "102_102") (pintype "passive+no_connect"))
    )
    (net (code "98") (name "unconnected-(J-Pad105)") (class "Default")
      (node (ref "J") (pin "105") (pinfunction "105_105") (pintype "passive+no_connect"))
    )
    (net (code "99") (name "unconnected-(J-Pad106)") (class "Default")
      (node (ref "J") (pin "106") (pinfunction "106_106") (pintype "passive+no_connect"))
    )
    (net (code "100") (name "unconnected-(J-Pad107)") (class "Default")
      (node (ref "J") (pin "107") (pinfunction "107_107") (pintype "passive+no_connect"))
    )
    (net (code "101") (name "unconnected-(J-Pad108)") (class "Default")
      (node (ref "J") (pin "108") (pinfunction "108_108") (pintype "passive+no_connect"))
    )
    (net (code "102") (name "unconnected-(J-Pad112)") (class "Default")
      (node (ref "J") (pin "112") (pinfunction "112_112") (pintype "passive+no_connect"))
    )
    (net (code "103") (name "unconnected-(J-Pad114)") (class "Default")
      (node (ref "J") (pin "114") (pinfunction "114_114") (pintype "passive+no_connect"))
    )
    (net (code "104") (name "unconnected-(J-Pad118)") (class "Default")
      (node (ref "J") (pin "118") (pinfunction "118_118") (pintype "passive+no_connect"))
    )
    (net (code "105") (name "unconnected-(J-Pad120)") (class "Default")
      (node (ref "J") (pin "120") (pinfunction "120_120") (pintype "passive+no_connect"))
    )
    (net (code "106") (name "unconnected-(J-Pad124)") (class "Default")
      (node (ref "J") (pin "124") (pinfunction "124_124") (pintype "passive+no_connect"))
    )
    (net (code "107") (name "unconnected-(J-Pad126)") (class "Default")
      (node (ref "J") (pin "126") (pinfunction "126_126") (pintype "passive+no_connect"))
    )
    (net (code "108") (name "unconnected-(J-Pad128)") (class "Default")
      (node (ref "J") (pin "128") (pinfunction "128_128") (pintype "passive+no_connect"))
    )
    (net (code "109") (name "unconnected-(J-Pad130)") (class "Default")
      (node (ref "J") (pin "130") (pinfunction "130_130") (pintype "passive+no_connect"))
    )
    (net (code "110") (name "unconnected-(J-Pad132)") (class "Default")
      (node (ref "J") (pin "132") (pinfunction "132_132") (pintype "passive+no_connect"))
    )
    (net (code "111") (name "unconnected-(J-Pad136)") (class "Default")
      (node (ref "J") (pin "136") (pinfunction "136_136") (pintype "passive+no_connect"))
    )
    (net (code "112") (name "unconnected-(J-Pad138)") (class "Default")
      (node (ref "J") (pin "138") (pinfunction "138_138") (pintype "passive+no_connect"))
    )
    (net (code "113") (name "unconnected-(J-Pad142)") (class "Default")
      (node (ref "J") (pin "142") (pinfunction "142_142") (pintype "passive+no_connect"))
    )
    (net (code "114") (name "unconnected-(J-Pad144)") (class "Default")
      (node (ref "J") (pin "144") (pinfunction "144_144") (pintype "passive+no_connect"))
    )
    (net (code "115") (name "unconnected-(J-Pad148)") (class "Default")
      (node (ref "J") (pin "148") (pinfunction "148_148") (pintype "passive+no_connect"))
    )
    (net (code "116") (name "unconnected-(J-Pad150)") (class "Default")
      (node (ref "J") (pin "150") (pinfunction "150_150") (pintype "passive+no_connect"))
    )
    (net (code "117") (name "unconnected-(J-Pad154)") (class "Default")
      (node (ref "J") (pin "154") (pinfunction "154_154") (pintype "passive+no_connect"))
    )
    (net (code "118") (name "unconnected-(J-Pad156)") (class "Default")
      (node (ref "J") (pin "156") (pinfunction "156_156") (pintype "passive+no_connect"))
    )
    (net (code "119") (name "unconnected-(J-Pad158)") (class "Default")
      (node (ref "J") (pin "158") (pinfunction "158_158") (pintype "passive+no_connect"))
    )
    (net (code "120") (name "unconnected-(J-Pad160)") (class "Default")
      (node (ref "J") (pin "160") (pinfunction "160_160") (pintype "passive+no_connect"))
    )
    (net (code "121") (name "unconnected-(J-Pad162)") (class "Default")
      (node (ref "J") (pin "162") (pinfunction "162_162") (pintype "passive+no_connect"))
    )
    (net (code "122") (name "unconnected-(J-Pad166)") (class "Default")
      (node (ref "J") (pin "166") (pinfunction "166_166") (pintype "passive+no_connect"))
    )
    (net (code "123") (name "unconnected-(J-Pad168)") (class "Default")
      (node (ref "J") (pin "168") (pinfunction "168_168") (pintype "passive+no_connect"))
    )
    (net (code "124") (name "unconnected-(J-Pad172)") (class "Default")
      (node (ref "J") (pin "172") (pinfunction "172_172") (pintype "passive+no_connect"))
    )
    (net (code "125") (name "unconnected-(J-Pad174)") (class "Default")
      (node (ref "J") (pin "174") (pinfunction "174_174") (pintype "passive+no_connect"))
    )
    (net (code "126") (name "unconnected-(J-Pad176)") (class "Default")
      (node (ref "J") (pin "176") (pinfunction "176_176") (pintype "passive+no_connect"))
    )
    (net (code "127") (name "unconnected-(J-Pad177)") (class "Default")
      (node (ref "J") (pin "177") (pinfunction "177_177") (pintype "passive+no_connect"))
    )
    (net (code "128") (name "unconnected-(J-Pad178)") (class "Default")
      (node (ref "J") (pin "178") (pinfunction "178_178") (pintype "passive+no_connect"))
    )
    (net (code "129") (name "unconnected-(J-Pad179)") (class "Default")
      (node (ref "J") (pin "179") (pinfunction "179_179") (pintype "passive+no_connect"))
    )
    (net (code "130") (name "unconnected-(J-Pad180)") (class "Default")
      (node (ref "J") (pin "180") (pinfunction "180_180") (pintype "passive+no_connect"))
    )
    (net (code "131") (name "unconnected-(J1-UTILITY-Pad2)") (class "Default")
      (node (ref "J1") (pin "2") (pinfunction "UTILITY_2") (pintype "passive+no_connect"))
    )
    (net (code "132") (name "unconnected-(J2-Pad17)") (class "Default")
      (node (ref "J2") (pin "17") (pinfunction "17_17") (pintype "passive+no_connect"))
    )
    (net (code "133") (name "unconnected-(J2-Pad18)") (class "Default")
      (node (ref "J2") (pin "18") (pinfunction "18_18") (pintype "passive+no_connect"))
    )
    (net (code "134") (name "unconnected-(J3-DN2-PadB7)") (class "Default")
      (node (ref "J3") (pin "B7") (pinfunction "DN2_B7") (pintype "bidirectional+no_connect"))
    )
    (net (code "135") (name "unconnected-(J3-DP2-PadB6)") (class "Default")
      (node (ref "J3") (pin "B6") (pinfunction "DP2_B6") (pintype "bidirectional+no_connect"))
    )
    (net (code "136") (name "unconnected-(J3-SBU1-PadA8)") (class "Default")
      (node (ref "J3") (pin "A8") (pinfunction "SBU1_A8") (pintype "bidirectional+no_connect"))
    )
    (net (code "137") (name "unconnected-(J3-SBU2-PadB8)") (class "Default")
      (node (ref "J3") (pin "B8") (pinfunction "SBU2_B8") (pintype "bidirectional+no_connect"))
    )
  )
)
